# 119_02a_INTELLIGENT_SENSOR_BOARD_FOR_MAN.net
KiCad netlist of a schematic drawn in EAGLE
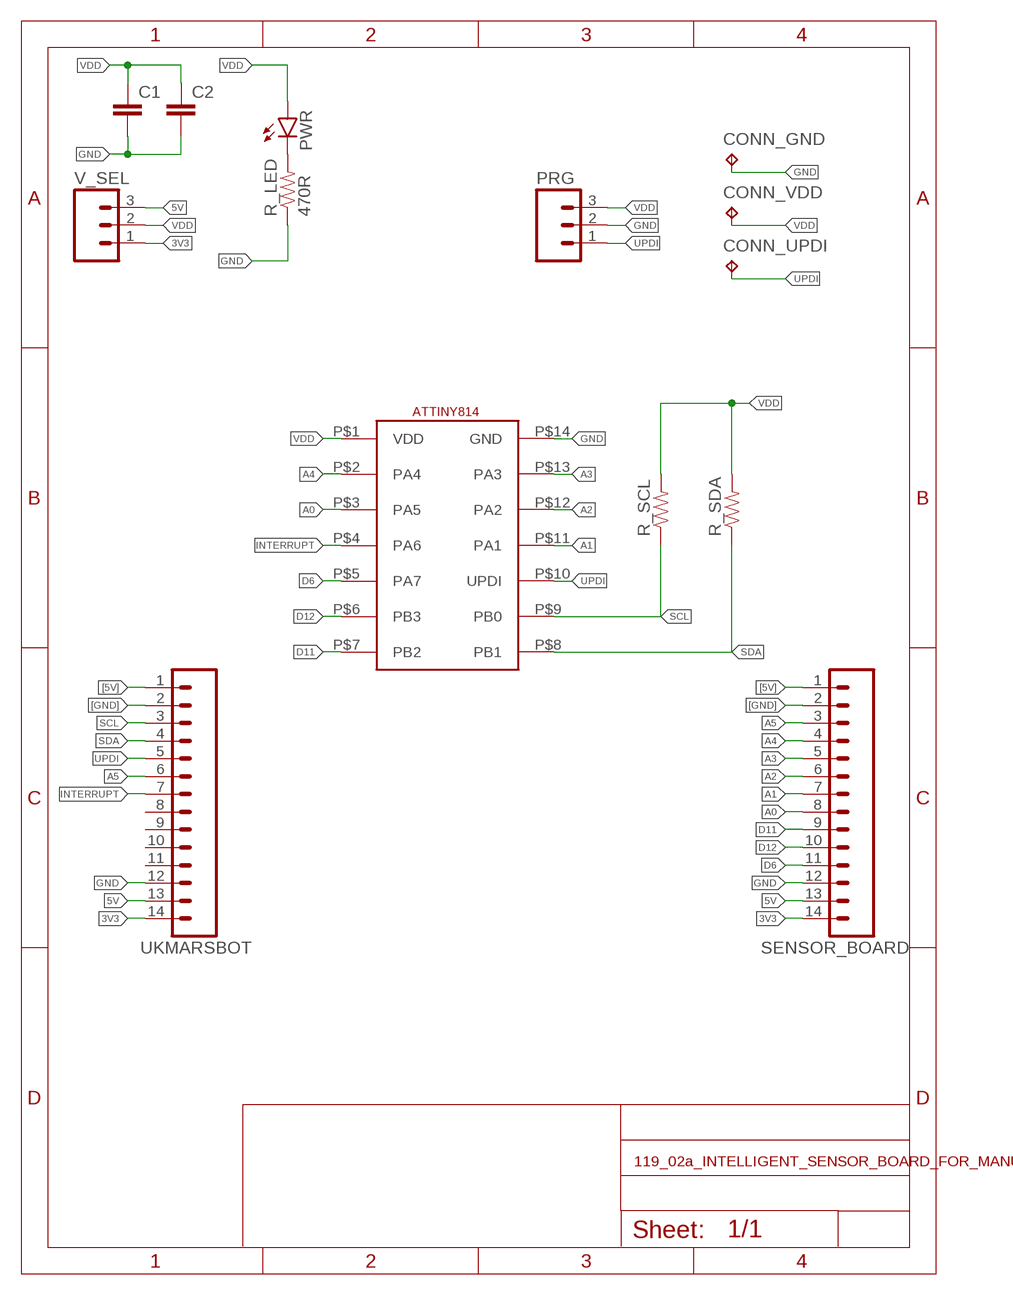
[diagram p0: schematic, sheet 1]

(export (version "E")
  (design (tool "Eeschema 10.0.6"))
  (components
    (comp (ref "C1")
      (value "CAP0805")
      (footprint "eagle-import:0805")
      (libsource (lib "eagle-import") (part "CAP0805"))
    )
    (comp (ref "C2")
      (value "CAP0805")
      (footprint "eagle-import:0805")
      (libsource (lib "eagle-import") (part "CAP0805"))
    )
    (comp (ref "CONN_GND")
      (value "TPB1,27")
      (footprint "eagle-import:B1,27")
      (libsource (lib "eagle-import") (part "TPB1,27"))
    )
    (comp (ref "CONN_UPDI")
      (value "TPB1,27")
      (footprint "eagle-import:B1,27")
      (libsource (lib "eagle-import") (part "TPB1,27"))
    )
    (comp (ref "CONN_VDD")
      (value "TPB1,27")
      (footprint "eagle-import:B1,27")
      (libsource (lib "eagle-import") (part "TPB1,27"))
    )
    (comp (ref "PRG")
      (value "M03PTH")
      (footprint "eagle-import:1X03")
      (libsource (lib "eagle-import") (part "M03PTH"))
    )
    (comp (ref "PWR")
      (value "LEDCHIP-LED0805")
      (footprint "eagle-import:CHIP-LED0805")
      (libsource (lib "eagle-import") (part "LEDCHIP-LED0805"))
    )
    (comp (ref "R_LED")
      (value "470R")
      (footprint "eagle-import:0805")
      (libsource (lib "eagle-import") (part "RESISTOR0805-RES"))
    )
    (comp (ref "R_SCL")
      (value "RESISTOR0805-RES")
      (footprint "eagle-import:0805")
      (libsource (lib "eagle-import") (part "RESISTOR0805-RES"))
    )
    (comp (ref "R_SDA")
      (value "RESISTOR0805-RES")
      (footprint "eagle-import:0805")
      (libsource (lib "eagle-import") (part "RESISTOR0805-RES"))
    )
    (comp (ref "SENSOR_BOARD")
      (value "M14")
      (footprint "eagle-import:1X14")
      (libsource (lib "eagle-import") (part "M14"))
    )
    (comp (ref "U$1")
      (value "ATTINY814")
      (footprint "eagle-import:ATTINY814")
      (libsource (lib "eagle-import") (part "ATTINY814"))
    )
    (comp (ref "UKMARSBOT")
      (value "M14")
      (footprint "eagle-import:1X14")
      (libsource (lib "eagle-import") (part "M14"))
    )
    (comp (ref "V_SEL")
      (value "M03PTH")
      (footprint "eagle-import:1X03")
      (libsource (lib "eagle-import") (part "M03PTH"))
    )
  )
  (nets
    (net (code "1") (name "3V3") (class "Default")
      (node (ref "SENSOR_BOARD") (pin "14") (pinfunction "14_14") (pintype "passive"))
      (node (ref "UKMARSBOT") (pin "14") (pinfunction "14_14") (pintype "passive"))
      (node (ref "V_SEL") (pin "1") (pinfunction "1_1") (pintype "passive"))
    )
    (net (code "2") (name "5V") (class "Default")
      (node (ref "SENSOR_BOARD") (pin "13") (pinfunction "13_13") (pintype "passive"))
      (node (ref "UKMARSBOT") (pin "13") (pinfunction "13_13") (pintype "passive"))
      (node (ref "V_SEL") (pin "3") (pinfunction "3_3") (pintype "passive"))
    )
    (net (code "3") (name "A0") (class "Default")
      (node (ref "SENSOR_BOARD") (pin "8") (pinfunction "8_8") (pintype "passive"))
      (node (ref "U$1") (pin "P$3") (pinfunction "PA5_P$3") (pintype "bidirectional"))
    )
    (net (code "4") (name "A1") (class "Default")
      (node (ref "SENSOR_BOARD") (pin "7") (pinfunction "7_7") (pintype "passive"))
      (node (ref "U$1") (pin "P$11") (pinfunction "PA1_P$11") (pintype "bidirectional"))
    )
    (net (code "5") (name "A2") (class "Default")
      (node (ref "SENSOR_BOARD") (pin "6") (pinfunction "6_6") (pintype "passive"))
      (node (ref "U$1") (pin "P$12") (pinfunction "PA2_P$12") (pintype "bidirectional"))
    )
    (net (code "6") (name "A3") (class "Default")
      (node (ref "SENSOR_BOARD") (pin "5") (pinfunction "5_5") (pintype "passive"))
      (node (ref "U$1") (pin "P$13") (pinfunction "PA3_P$13") (pintype "bidirectional"))
    )
    (net (code "7") (name "A4") (class "Default")
      (node (ref "SENSOR_BOARD") (pin "4") (pinfunction "4_4") (pintype "passive"))
      (node (ref "U$1") (pin "P$2") (pinfunction "PA4_P$2") (pintype "bidirectional"))
    )
    (net (code "8") (name "A5") (class "Default")
      (node (ref "SENSOR_BOARD") (pin "3") (pinfunction "3_3") (pintype "passive"))
      (node (ref "UKMARSBOT") (pin "6") (pinfunction "6_6") (pintype "passive"))
    )
    (net (code "9") (name "D6") (class "Default")
      (node (ref "SENSOR_BOARD") (pin "11") (pinfunction "11_11") (pintype "passive"))
      (node (ref "U$1") (pin "P$5") (pinfunction "PA7_P$5") (pintype "bidirectional"))
    )
    (net (code "10") (name "D11") (class "Default")
      (node (ref "SENSOR_BOARD") (pin "9") (pinfunction "9_9") (pintype "passive"))
      (node (ref "U$1") (pin "P$7") (pinfunction "PB2_P$7") (pintype "bidirectional"))
    )
    (net (code "11") (name "D12") (class "Default")
      (node (ref "SENSOR_BOARD") (pin "10") (pinfunction "10_10") (pintype "passive"))
      (node (ref "U$1") (pin "P$6") (pinfunction "PB3_P$6") (pintype "bidirectional"))
    )
    (net (code "12") (name "GND") (class "Default")
      (node (ref "C1") (pin "2") (pinfunction "2_2") (pintype "passive"))
      (node (ref "C2") (pin "2") (pinfunction "2_2") (pintype "passive"))
      (node (ref "CONN_GND") (pin "TP") (pinfunction "TP_TP") (pintype "input"))
      (node (ref "PRG") (pin "2") (pinfunction "2_2") (pintype "passive"))
      (node (ref "R_LED") (pin "1") (pinfunction "1_1") (pintype "passive"))
      (node (ref "SENSOR_BOARD") (pin "12") (pinfunction "12_12") (pintype "passive"))
      (node (ref "U$1") (pin "P$14") (pinfunction "GND_P$14") (pintype "bidirectional"))
      (node (ref "UKMARSBOT") (pin "12") (pinfunction "12_12") (pintype "passive"))
    )
    (net (code "13") (name "INTERRUPT") (class "Default")
      (node (ref "U$1") (pin "P$4") (pinfunction "PA6_P$4") (pintype "bidirectional"))
      (node (ref "UKMARSBOT") (pin "7") (pinfunction "7_7") (pintype "passive"))
    )
    (net (code "14") (name "Net-(PWR-PadC)") (class "Default")
      (node (ref "PWR") (pin "C") (pinfunction "C_C") (pintype "passive"))
      (node (ref "R_LED") (pin "2") (pinfunction "2_2") (pintype "passive"))
    )
    (net (code "15") (name "SCL") (class "Default")
      (node (ref "R_SCL") (pin "1") (pinfunction "1_1") (pintype "passive"))
      (node (ref "U$1") (pin "P$9") (pinfunction "PB0_P$9") (pintype "bidirectional"))
      (node (ref "UKMARSBOT") (pin "3") (pinfunction "3_3") (pintype "passive"))
    )
    (net (code "16") (name "SDA") (class "Default")
      (node (ref "R_SDA") (pin "1") (pinfunction "1_1") (pintype "passive"))
      (node (ref "U$1") (pin "P$8") (pinfunction "PB1_P$8") (pintype "bidirectional"))
      (node (ref "UKMARSBOT") (pin "4") (pinfunction "4_4") (pintype "passive"))
    )
    (net (code "17") (name "UPDI") (class "Default")
      (node (ref "CONN_UPDI") (pin "TP") (pinfunction "TP_TP") (pintype "input"))
      (node (ref "PRG") (pin "1") (pinfunction "1_1") (pintype "passive"))
      (node (ref "U$1") (pin "P$10") (pinfunction "UPDI_P$10") (pintype "bidirectional"))
      (node (ref "UKMARSBOT") (pin "5") (pinfunction "5_5") (pintype "passive"))
    )
    (net (code "18") (name "VDD") (class "Default")
      (node (ref "C1") (pin "1") (pinfunction "1_1") (pintype "passive"))
      (node (ref "C2") (pin "1") (pinfunction "1_1") (pintype "passive"))
      (node (ref "CONN_VDD") (pin "TP") (pinfunction "TP_TP") (pintype "input"))
      (node (ref "PRG") (pin "3") (pinfunction "3_3") (pintype "passive"))
      (node (ref "PWR") (pin "A") (pinfunction "A_A") (pintype "passive"))
      (node (ref "R_SCL") (pin "2") (pinfunction "2_2") (pintype "passive"))
      (node (ref "R_SDA") (pin "2") (pinfunction "2_2") (pintype "passive"))
      (node (ref "U$1") (pin "P$1") (pinfunction "VDD_P$1") (pintype "bidirectional"))
      (node (ref "V_SEL") (pin "2") (pinfunction "2_2") (pintype "passive"))
    )
    (net (code "19") (name "[5V]") (class "Default")
      (node (ref "SENSOR_BOARD") (pin "1") (pinfunction "1_1") (pintype "passive"))
      (node (ref "UKMARSBOT") (pin "1") (pinfunction "1_1") (pintype "passive"))
    )
    (net (code "20") (name "[GND]") (class "Default")
      (node (ref "SENSOR_BOARD") (pin "2") (pinfunction "2_2") (pintype "passive"))
      (node (ref "UKMARSBOT") (pin "2") (pinfunction "2_2") (pintype "passive"))
    )
    (net (code "21") (name "unconnected-(UKMARSBOT-Pad8)") (class "Default")
      (node (ref "UKMARSBOT") (pin "8") (pinfunction "8_8") (pintype "passive"))
    )
    (net (code "22") (name "unconnected-(UKMARSBOT-Pad9)") (class "Default")
      (node (ref "UKMARSBOT") (pin "9") (pinfunction "9_9") (pintype "passive"))
    )
    (net (code "23") (name "unconnected-(UKMARSBOT-Pad10)") (class "Default")
      (node (ref "UKMARSBOT") (pin "10") (pinfunction "10_10") (pintype "passive"))
    )
    (net (code "24") (name "unconnected-(UKMARSBOT-Pad11)") (class "Default")
      (node (ref "UKMARSBOT") (pin "11") (pinfunction "11_11") (pintype "passive"))
    )
  )
)
